# cp2102_usbC.net
KiCad netlist of a schematic drawn in Altium Designer
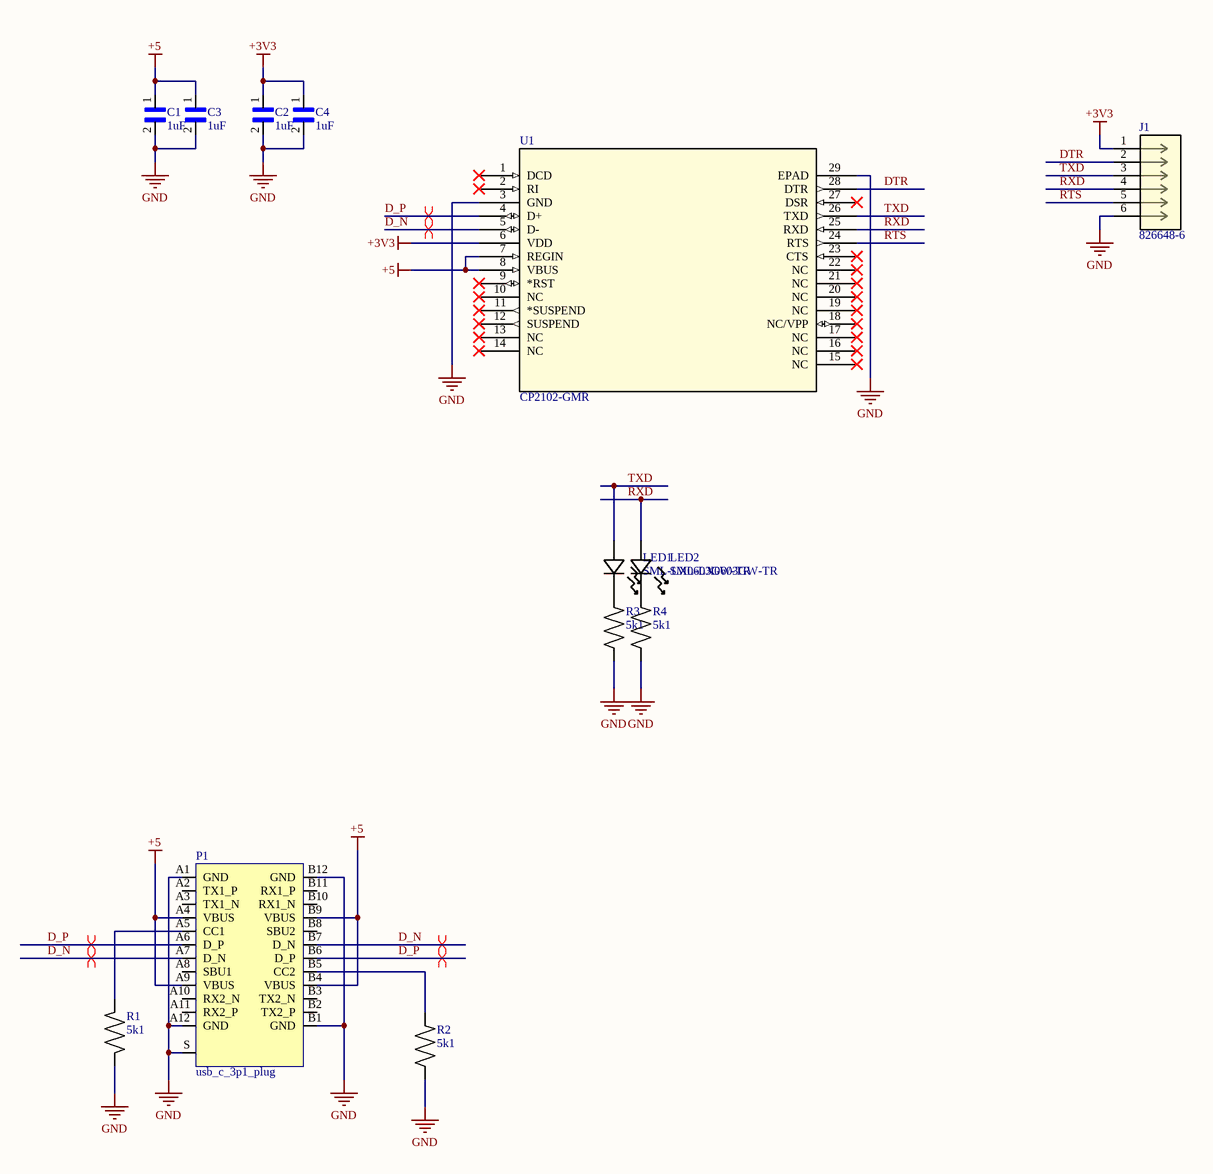
[diagram p0: cp2102_usbC.SchDoc]

(export (version "E")
  (design (tool "Eeschema 10.0.6"))
  (components
    (comp (ref "C1")
      (value "1uF")
      (footprint "*CAPC1608X90N")
      (description "0603 10 nF 25 V 10% Tolerance X7R Surface Mount Multilayer Ceramic Capacitor")
      (fields (field (name "MP") "06033C103KAT2A") (field (name "MF") "AVX"))
      (libsource (lib "06033C103KAT2A") (part "06033C103KAT2A"))
    )
    (comp (ref "C2")
      (value "1uF")
      (footprint "*CAPC1608X90N")
      (description "0603 10 nF 25 V 10% Tolerance X7R Surface Mount Multilayer Ceramic Capacitor")
      (fields (field (name "MP") "06033C103KAT2A") (field (name "MF") "AVX"))
      (libsource (lib "06033C103KAT2A") (part "06033C103KAT2A"))
    )
    (comp (ref "C3")
      (value "1uF")
      (footprint "*CAPC1608X90N")
      (description "0603 10 nF 25 V 10% Tolerance X7R Surface Mount Multilayer Ceramic Capacitor")
      (fields (field (name "MP") "06033C103KAT2A") (field (name "MF") "AVX"))
      (libsource (lib "06033C103KAT2A") (part "06033C103KAT2A"))
    )
    (comp (ref "C4")
      (value "1uF")
      (footprint "*CAPC1608X90N")
      (description "0603 10 nF 25 V 10% Tolerance X7R Surface Mount Multilayer Ceramic Capacitor")
      (fields (field (name "MP") "06033C103KAT2A") (field (name "MF") "AVX"))
      (libsource (lib "06033C103KAT2A") (part "06033C103KAT2A"))
    )
    (comp (ref "J1")
      (value "826648-6")
      (footprint "CONN6_826648-6_TEC")
      (description "6P AMPMODU II STIFT LEI")
      (fields (field (name "COPYRIGHT") "Copyright (C) 2016 Accelerated Designs. All rights reserved"))
      (libsource (lib "8266486") (part "826648-6"))
    )
    (comp (ref "LED1")
      (value "SML-LX0603GW-TR")
      (footprint "LED_SML-LX0603GW-TR_LUM")
      (description "No Description Available")
      (fields (field (name "COPYRIGHT") "Copyright (C) 2018 Accelerated Designs. All rights reserved"))
      (libsource (lib "2020-11-02_17-20-17") (part "SML-LX0603GW-TR"))
    )
    (comp (ref "LED2")
      (value "SML-LX0603GW-TR")
      (footprint "LED_SML-LX0603GW-TR_LUM")
      (description "No Description Available")
      (fields (field (name "COPYRIGHT") "Copyright (C) 2018 Accelerated Designs. All rights reserved"))
      (libsource (lib "2020-11-02_17-20-17") (part "SML-LX0603GW-TR"))
    )
    (comp (ref "P1")
      (value "usb_c_3p1_plug")
      (footprint "PCBComponent_1")
      (libsource (lib "usb_c_3p1_plug") (part "usb_c_3p1_plug"))
    )
    (comp (ref "R1")
      (value "5k1")
      (footprint "*RESC1608X55N")
      (description "Res Thick Film 0603 4.7K Ohm 1% 1/10W 100ppm/C Molded SMD SMD Paper Tape on Plastic Reel")
      (fields (field (name "MP") "CR0603-FX-4701ELF") (field (name "MF") "Bourns"))
      (libsource (lib "CR0603-FX-4701ELF") (part "CR0603-FX-4701ELF"))
    )
    (comp (ref "R2")
      (value "5k1")
      (footprint "*RESC1608X55N")
      (description "Res Thick Film 0603 4.7K Ohm 1% 1/10W 100ppm/C Molded SMD SMD Paper Tape on Plastic Reel")
      (fields (field (name "MP") "CR0603-FX-4701ELF") (field (name "MF") "Bourns"))
      (libsource (lib "CR0603-FX-4701ELF") (part "CR0603-FX-4701ELF"))
    )
    (comp (ref "R3")
      (value "5k1")
      (footprint "*RESC1608X55N")
      (description "Res Thick Film 0603 4.7K Ohm 1% 1/10W 100ppm/C Molded SMD SMD Paper Tape on Plastic Reel")
      (fields (field (name "MP") "CR0603-FX-4701ELF") (field (name "MF") "Bourns"))
      (libsource (lib "CR0603-FX-4701ELF") (part "CR0603-FX-4701ELF"))
    )
    (comp (ref "R4")
      (value "5k1")
      (footprint "*RESC1608X55N")
      (description "Res Thick Film 0603 4.7K Ohm 1% 1/10W 100ppm/C Molded SMD SMD Paper Tape on Plastic Reel")
      (fields (field (name "MP") "CR0603-FX-4701ELF") (field (name "MF") "Bourns"))
      (libsource (lib "CR0603-FX-4701ELF") (part "CR0603-FX-4701ELF"))
    )
    (comp (ref "U1")
      (value "CP2102-GMR")
      (footprint "QFN28_5X5_SIL")
      (description "No Description Available")
      (fields (field (name "COPYRIGHT") "Copyright (C) 2018 Accelerated Designs. All rights reserved"))
      (libsource (lib "CP2102GMR") (part "CP2102-GMR"))
    )
  )
  (nets
    (net (code "1") (name "+3V3") (class "Default")
      (node (ref "C2") (pin "1") (pinfunction "1_1") (pintype "passive"))
      (node (ref "C4") (pin "1") (pinfunction "1_1") (pintype "passive"))
      (node (ref "J1") (pin "1") (pinfunction "1_1") (pintype "passive"))
      (node (ref "U1") (pin "6") (pinfunction "VDD_6") (pintype "power_in"))
    )
    (net (code "2") (name "+5") (class "Default")
      (node (ref "C1") (pin "1") (pinfunction "1_1") (pintype "passive"))
      (node (ref "C3") (pin "1") (pinfunction "1_1") (pintype "passive"))
      (node (ref "P1") (pin "A4") (pinfunction "VBUS_A4") (pintype "passive"))
      (node (ref "P1") (pin "A9") (pinfunction "VBUS_A9") (pintype "passive"))
      (node (ref "P1") (pin "B4") (pinfunction "VBUS_B4") (pintype "passive"))
      (node (ref "P1") (pin "B9") (pinfunction "VBUS_B9") (pintype "passive"))
      (node (ref "U1") (pin "7") (pinfunction "REGIN_7") (pintype "input"))
      (node (ref "U1") (pin "8") (pinfunction "VBUS_8") (pintype "input"))
    )
    (net (code "3") (name "/DTR") (class "Default")
      (node (ref "J1") (pin "2") (pinfunction "2_2") (pintype "passive"))
      (node (ref "U1") (pin "28") (pinfunction "DTR_28") (pintype "output"))
    )
    (net (code "4") (name "/D_N") (class "Default")
      (node (ref "P1") (pin "A7") (pinfunction "D_N_A7") (pintype "passive"))
      (node (ref "P1") (pin "B7") (pinfunction "D_N_B7") (pintype "passive"))
      (node (ref "U1") (pin "5") (pinfunction "D-_5") (pintype "bidirectional"))
    )
    (net (code "5") (name "/D_P") (class "Default")
      (node (ref "P1") (pin "A6") (pinfunction "D_P_A6") (pintype "passive"))
      (node (ref "P1") (pin "B6") (pinfunction "D_P_B6") (pintype "passive"))
      (node (ref "U1") (pin "4") (pinfunction "D+_4") (pintype "bidirectional"))
    )
    (net (code "6") (name "/RTS") (class "Default")
      (node (ref "J1") (pin "5") (pinfunction "5_5") (pintype "passive"))
      (node (ref "U1") (pin "24") (pinfunction "RTS_24") (pintype "output"))
    )
    (net (code "7") (name "/RXD") (class "Default")
      (node (ref "J1") (pin "4") (pinfunction "4_4") (pintype "passive"))
      (node (ref "LED2") (pin "2") (pinfunction "2_2") (pintype "passive"))
      (node (ref "U1") (pin "25") (pinfunction "RXD_25") (pintype "input"))
    )
    (net (code "8") (name "/TXD") (class "Default")
      (node (ref "J1") (pin "3") (pinfunction "3_3") (pintype "passive"))
      (node (ref "LED1") (pin "2") (pinfunction "2_2") (pintype "passive"))
      (node (ref "U1") (pin "26") (pinfunction "TXD_26") (pintype "output"))
    )
    (net (code "9") (name "GND") (class "Default")
      (node (ref "C1") (pin "2") (pinfunction "2_2") (pintype "passive"))
      (node (ref "C2") (pin "2") (pinfunction "2_2") (pintype "passive"))
      (node (ref "C3") (pin "2") (pinfunction "2_2") (pintype "passive"))
      (node (ref "C4") (pin "2") (pinfunction "2_2") (pintype "passive"))
      (node (ref "J1") (pin "6") (pinfunction "6_6") (pintype "passive"))
      (node (ref "P1") (pin "A1") (pinfunction "GND_A1") (pintype "power_in"))
      (node (ref "P1") (pin "A12") (pinfunction "GND_A12") (pintype "power_in"))
      (node (ref "P1") (pin "B1") (pinfunction "GND_B1") (pintype "passive"))
      (node (ref "P1") (pin "B12") (pinfunction "GND_B12") (pintype "power_in"))
      (node (ref "P1") (pin "S") (pinfunction "SHIELD_S") (pintype "passive"))
      (node (ref "R1") (pin "1") (pinfunction "1_1") (pintype "passive"))
      (node (ref "R2") (pin "1") (pinfunction "1_1") (pintype "passive"))
      (node (ref "R3") (pin "1") (pinfunction "1_1") (pintype "passive"))
      (node (ref "R4") (pin "1") (pinfunction "1_1") (pintype "passive"))
      (node (ref "U1") (pin "29") (pinfunction "EPAD_29") (pintype "passive"))
      (node (ref "U1") (pin "3") (pinfunction "GND_3") (pintype "power_in"))
    )
    (net (code "10") (name "Net-(LED1-Pad1)") (class "Default")
      (node (ref "LED1") (pin "1") (pinfunction "1_1") (pintype "passive"))
      (node (ref "R3") (pin "2") (pinfunction "2_2") (pintype "passive"))
    )
    (net (code "11") (name "Net-(LED2-Pad1)") (class "Default")
      (node (ref "LED2") (pin "1") (pinfunction "1_1") (pintype "passive"))
      (node (ref "R4") (pin "2") (pinfunction "2_2") (pintype "passive"))
    )
    (net (code "12") (name "Net-(P1-CC1)") (class "Default")
      (node (ref "P1") (pin "A5") (pinfunction "CC1_A5") (pintype "passive"))
      (node (ref "R1") (pin "2") (pinfunction "2_2") (pintype "passive"))
    )
    (net (code "13") (name "Net-(P1-CC2)") (class "Default")
      (node (ref "P1") (pin "B5") (pinfunction "CC2_B5") (pintype "passive"))
      (node (ref "R2") (pin "2") (pinfunction "2_2") (pintype "passive"))
    )
    (net (code "14") (name "unconnected-(P1-RX1_N-PadB10)") (class "Default")
      (node (ref "P1") (pin "B10") (pinfunction "RX1_N_B10") (pintype "passive"))
    )
    (net (code "15") (name "unconnected-(P1-RX1_P-PadB11)") (class "Default")
      (node (ref "P1") (pin "B11") (pinfunction "RX1_P_B11") (pintype "passive"))
    )
    (net (code "16") (name "unconnected-(P1-RX2_N-PadA10)") (class "Default")
      (node (ref "P1") (pin "A10") (pinfunction "RX2_N_A10") (pintype "passive"))
    )
    (net (code "17") (name "unconnected-(P1-RX2_P-PadA11)") (class "Default")
      (node (ref "P1") (pin "A11") (pinfunction "RX2_P_A11") (pintype "passive"))
    )
    (net (code "18") (name "unconnected-(P1-SBU1-PadA8)") (class "Default")
      (node (ref "P1") (pin "A8") (pinfunction "SBU1_A8") (pintype "passive"))
    )
    (net (code "19") (name "unconnected-(P1-SBU2-PadB8)") (class "Default")
      (node (ref "P1") (pin "B8") (pinfunction "SBU2_B8") (pintype "passive"))
    )
    (net (code "20") (name "unconnected-(P1-TX1_N-PadA3)") (class "Default")
      (node (ref "P1") (pin "A3") (pinfunction "TX1_N_A3") (pintype "passive"))
    )
    (net (code "21") (name "unconnected-(P1-TX1_P-PadA2)") (class "Default")
      (node (ref "P1") (pin "A2") (pinfunction "TX1_P_A2") (pintype "power_in"))
    )
    (net (code "22") (name "unconnected-(P1-TX2_N-PadB3)") (class "Default")
      (node (ref "P1") (pin "B3") (pinfunction "TX2_N_B3") (pintype "passive"))
    )
    (net (code "23") (name "unconnected-(P1-TX2_P-PadB2)") (class "Default")
      (node (ref "P1") (pin "B2") (pinfunction "TX2_P_B2") (pintype "passive"))
    )
    (net (code "24") (name "unconnected-(U1-*RST-Pad9)") (class "Default")
      (node (ref "U1") (pin "9") (pinfunction "*RST_9") (pintype "bidirectional+no_connect"))
    )
    (net (code "25") (name "unconnected-(U1-*SUSPEND-Pad11)") (class "Default")
      (node (ref "U1") (pin "11") (pinfunction "*SUSPEND_11") (pintype "output+no_connect"))
    )
    (net (code "26") (name "unconnected-(U1-CTS-Pad23)") (class "Default")
      (node (ref "U1") (pin "23") (pinfunction "CTS_23") (pintype "input+no_connect"))
    )
    (net (code "27") (name "unconnected-(U1-DCD-Pad1)") (class "Default")
      (node (ref "U1") (pin "1") (pinfunction "DCD_1") (pintype "input+no_connect"))
    )
    (net (code "28") (name "unconnected-(U1-DSR-Pad27)") (class "Default")
      (node (ref "U1") (pin "27") (pinfunction "DSR_27") (pintype "input+no_connect"))
    )
    (net (code "29") (name "unconnected-(U1-NC-Pad10)") (class "Default")
      (node (ref "U1") (pin "10") (pinfunction "NC_10") (pintype "passive+no_connect"))
    )
    (net (code "30") (name "unconnected-(U1-NC-Pad13)") (class "Default")
      (node (ref "U1") (pin "13") (pinfunction "NC_13") (pintype "passive+no_connect"))
    )
    (net (code "31") (name "unconnected-(U1-NC-Pad14)") (class "Default")
      (node (ref "U1") (pin "14") (pinfunction "NC_14") (pintype "passive+no_connect"))
    )
    (net (code "32") (name "unconnected-(U1-NC-Pad15)") (class "Default")
      (node (ref "U1") (pin "15") (pinfunction "NC_15") (pintype "passive+no_connect"))
    )
    (net (code "33") (name "unconnected-(U1-NC-Pad16)") (class "Default")
      (node (ref "U1") (pin "16") (pinfunction "NC_16") (pintype "passive+no_connect"))
    )
    (net (code "34") (name "unconnected-(U1-NC-Pad17)") (class "Default")
      (node (ref "U1") (pin "17") (pinfunction "NC_17") (pintype "passive+no_connect"))
    )
    (net (code "35") (name "unconnected-(U1-NC-Pad19)") (class "Default")
      (node (ref "U1") (pin "19") (pinfunction "NC_19") (pintype "passive+no_connect"))
    )
    (net (code "36") (name "unconnected-(U1-NC-Pad20)") (class "Default")
      (node (ref "U1") (pin "20") (pinfunction "NC_20") (pintype "passive+no_connect"))
    )
    (net (code "37") (name "unconnected-(U1-NC-Pad21)") (class "Default")
      (node (ref "U1") (pin "21") (pinfunction "NC_21") (pintype "passive+no_connect"))
    )
    (net (code "38") (name "unconnected-(U1-NC-Pad22)") (class "Default")
      (node (ref "U1") (pin "22") (pinfunction "NC_22") (pintype "passive+no_connect"))
    )
    (net (code "39") (name "unconnected-(U1-NC{slash}VPP-Pad18)") (class "Default")
      (node (ref "U1") (pin "18") (pinfunction "NC/VPP_18") (pintype "bidirectional+no_connect"))
    )
    (net (code "40") (name "unconnected-(U1-RI-Pad2)") (class "Default")
      (node (ref "U1") (pin "2") (pinfunction "RI_2") (pintype "input+no_connect"))
    )
    (net (code "41") (name "unconnected-(U1-SUSPEND-Pad12)") (class "Default")
      (node (ref "U1") (pin "12") (pinfunction "SUSPEND_12") (pintype "output+no_connect"))
    )
  )
)
